# tugas_1_schematic.net
KiCad netlist of a schematic drawn in EAGLE
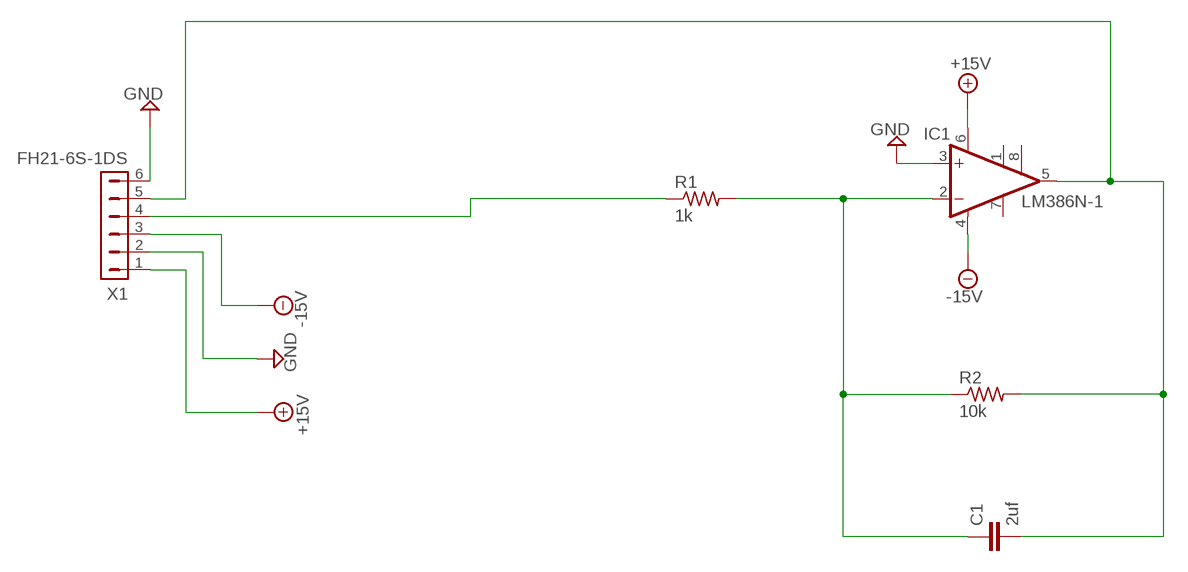
[diagram p0: schematic, sheet 1]

(export (version "E")
  (design (tool "Eeschema 10.0.6"))
  (components
    (comp (ref "C1")
      (value "2uf")
      (footprint "eagle-import:C0603")
      (libsource (lib "eagle-import") (part "C-EUC0603"))
    )
    (comp (ref "IC1")
      (value "LM386N-1")
      (footprint "eagle-import:DIL08")
      (libsource (lib "eagle-import") (part "LM386?-N1"))
    )
    (comp (ref "R1")
      (value "1k")
      (footprint "eagle-import:R0603")
      (libsource (lib "eagle-import") (part "R-US_R0603"))
    )
    (comp (ref "R2")
      (value "10k")
      (footprint "eagle-import:R0603")
      (libsource (lib "eagle-import") (part "R-US_R0603"))
    )
    (comp (ref "X1")
      (value "FH21-6S-1DS")
      (footprint "eagle-import:FH21-6S-1DS")
      (libsource (lib "eagle-import") (part "FH21-6S-1DS"))
    )
  )
  (nets
    (net (code "1") (name "+15V") (class "Default")
      (node (ref "IC1") (pin "6") (pinfunction "VS_6") (pintype "power_in"))
      (node (ref "X1") (pin "1") (pinfunction "1_1") (pintype "passive"))
    )
    (net (code "2") (name "-15V") (class "Default")
      (node (ref "IC1") (pin "4") (pinfunction "GND_4") (pintype "power_in"))
      (node (ref "X1") (pin "3") (pinfunction "3_3") (pintype "passive"))
    )
    (net (code "3") (name "GND") (class "Default")
      (node (ref "IC1") (pin "3") (pinfunction "+IN_3") (pintype "input"))
      (node (ref "X1") (pin "2") (pinfunction "2_2") (pintype "passive"))
      (node (ref "X1") (pin "6") (pinfunction "6_6") (pintype "passive"))
    )
    (net (code "4") (name "Net-(IC1--IN)") (class "Default")
      (node (ref "C1") (pin "1") (pinfunction "1_1") (pintype "passive"))
      (node (ref "IC1") (pin "2") (pinfunction "-IN_2") (pintype "input"))
      (node (ref "R1") (pin "2") (pinfunction "2_2") (pintype "passive"))
      (node (ref "R2") (pin "1") (pinfunction "1_1") (pintype "passive"))
    )
    (net (code "5") (name "Net-(IC1-OUT)") (class "Default")
      (node (ref "C1") (pin "2") (pinfunction "2_2") (pintype "passive"))
      (node (ref "IC1") (pin "5") (pinfunction "OUT_5") (pintype "output"))
      (node (ref "R2") (pin "2") (pinfunction "2_2") (pintype "passive"))
      (node (ref "X1") (pin "5") (pinfunction "5_5") (pintype "passive"))
    )
    (net (code "6") (name "Net-(R1-Pad1)") (class "Default")
      (node (ref "R1") (pin "1") (pinfunction "1_1") (pintype "passive"))
      (node (ref "X1") (pin "4") (pinfunction "4_4") (pintype "passive"))
    )
    (net (code "7") (name "unconnected-(IC1-BYPASS-Pad7)") (class "Default")
      (node (ref "IC1") (pin "7") (pinfunction "BYPASS_7") (pintype "passive"))
    )
    (net (code "8") (name "unconnected-(IC1-GAIN-Pad1)") (class "Default")
      (node (ref "IC1") (pin "1") (pinfunction "GAIN_1") (pintype "passive"))
    )
    (net (code "9") (name "unconnected-(IC1-GAIN-Pad8)") (class "Default")
      (node (ref "IC1") (pin "8") (pinfunction "GAIN_8") (pintype "passive"))
    )
  )
)
